# modulator-switch.net
KiCad netlist of a schematic drawn in EAGLE
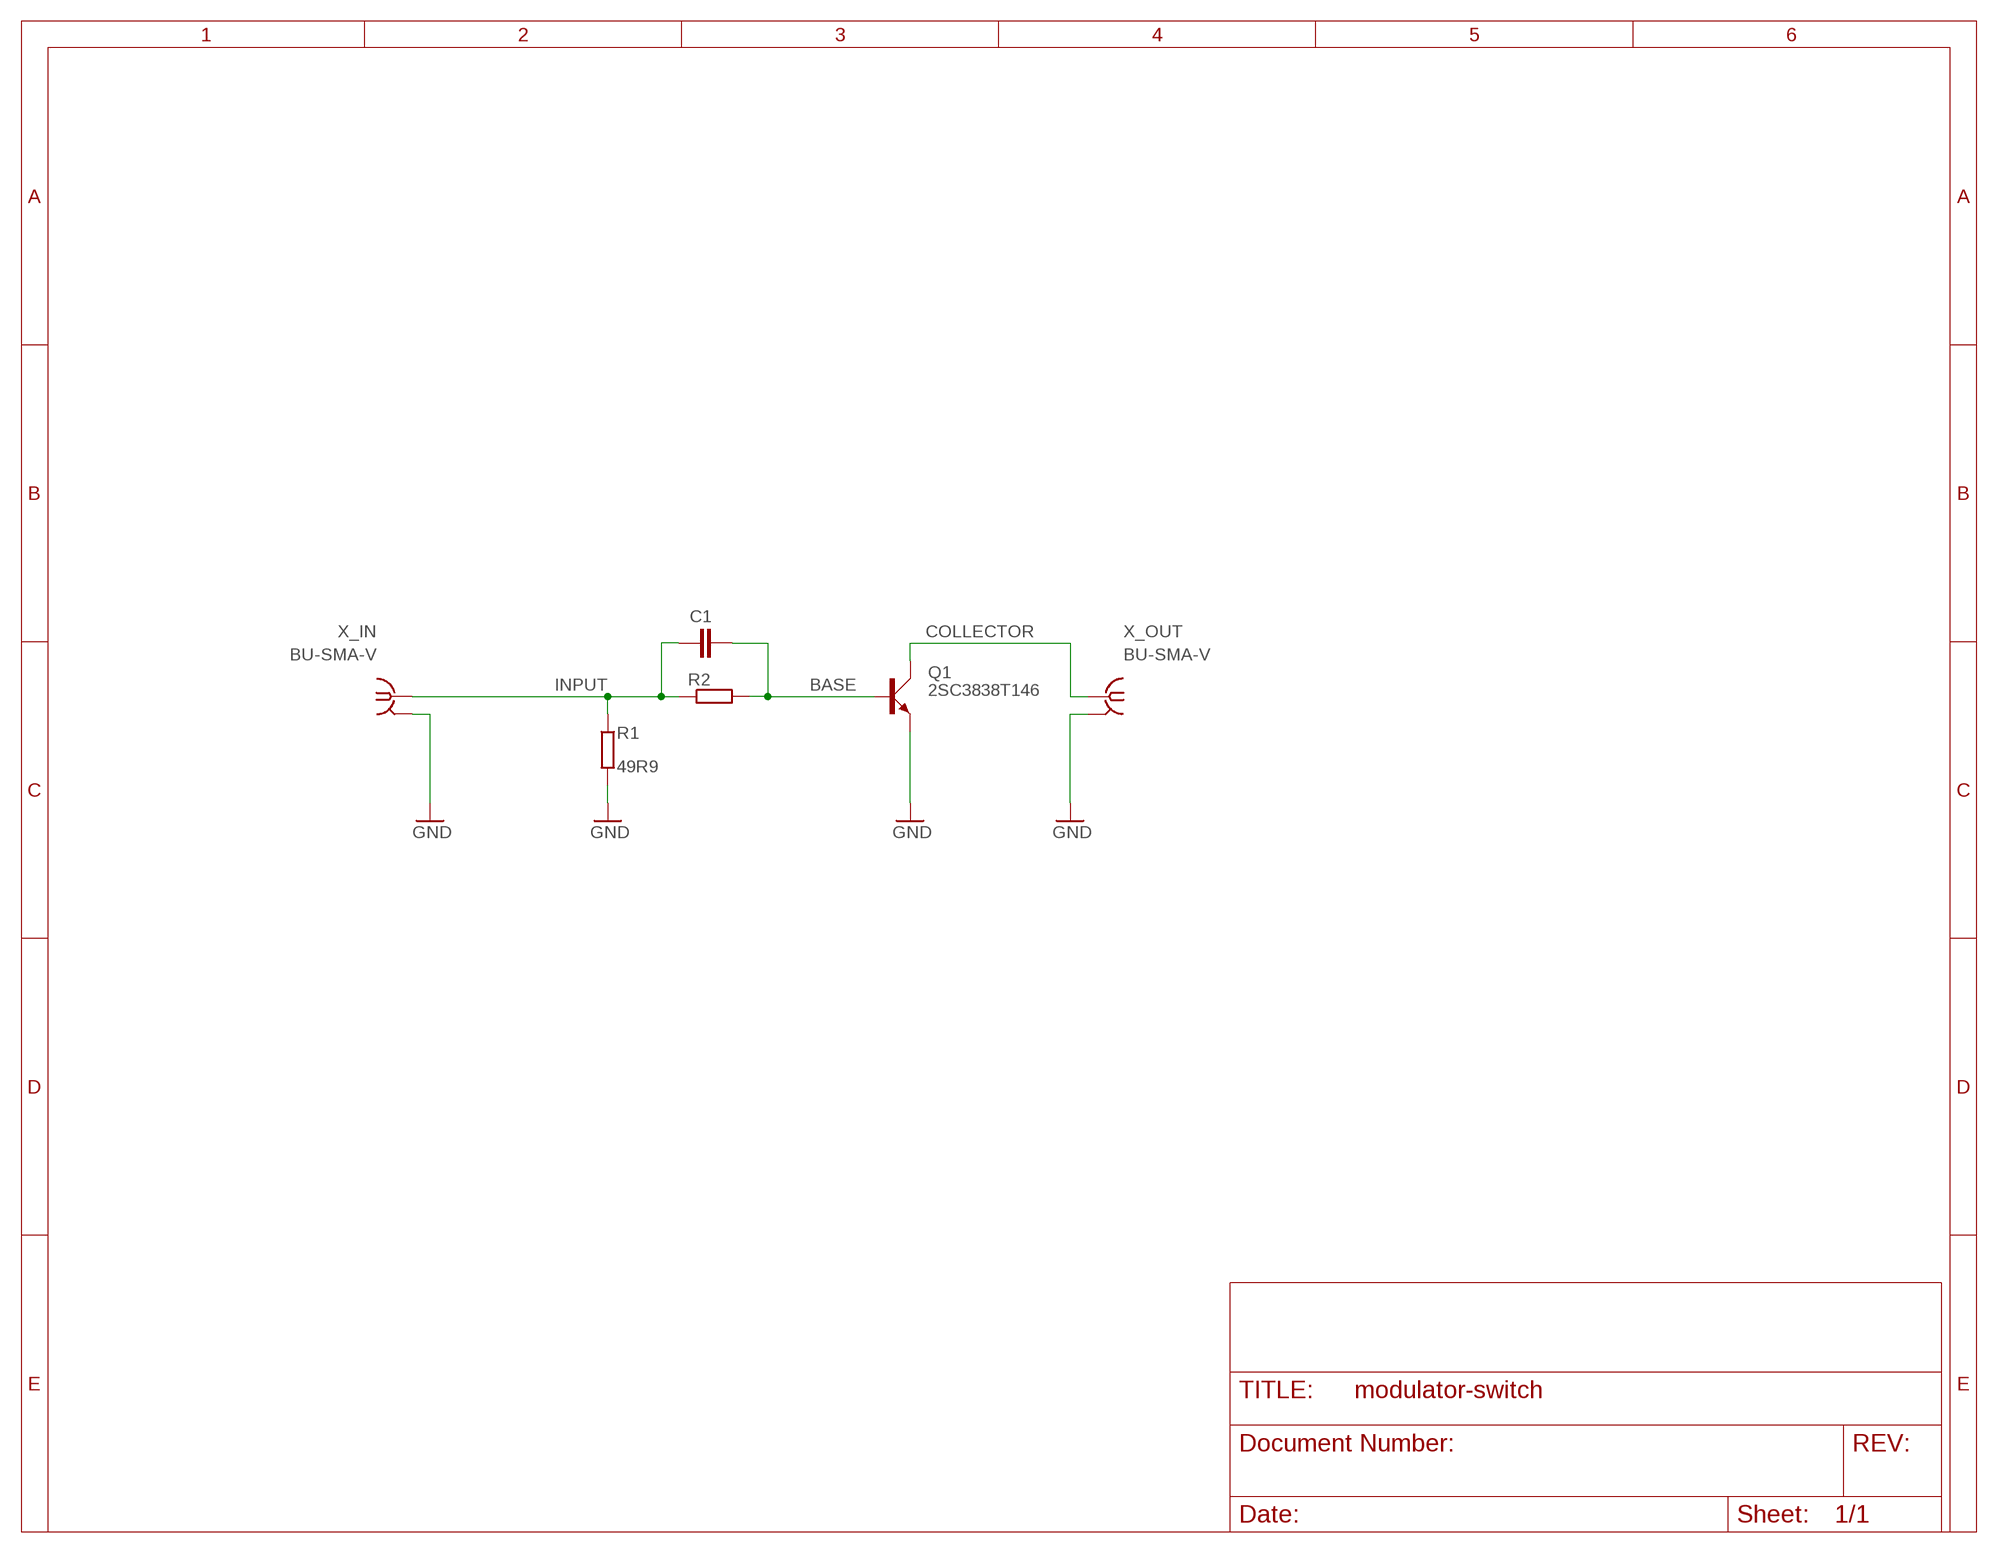
[diagram p0: schematic, sheet 1]

(export (version "E")
  (design (tool "Eeschema 10.0.6"))
  (components
    (comp (ref "C1")
      (value "C-EUC0603")
      (footprint "eagle-import:C0603")
      (libsource (lib "eagle-import") (part "C-EUC0603"))
    )
    (comp (ref "Q1")
      (value "2SC3838T146")
      (footprint "eagle-import:SC59")
      (libsource (lib "eagle-import") (part "2SC3838T146"))
    )
    (comp (ref "R1")
      (value "49R9")
      (footprint "eagle-import:R0805")
      (libsource (lib "eagle-import") (part "R-EU_R0805"))
    )
    (comp (ref "R2")
      (value "R-EU_R0603")
      (footprint "eagle-import:R0603")
      (libsource (lib "eagle-import") (part "R-EU_R0603"))
    )
    (comp (ref "X_IN")
      (value "BU-SMA-V")
      (footprint "eagle-import:BU-SMA-V")
      (libsource (lib "eagle-import") (part "BU-SMA-V"))
    )
    (comp (ref "X_OUT")
      (value "BU-SMA-V")
      (footprint "eagle-import:BU-SMA-V")
      (libsource (lib "eagle-import") (part "BU-SMA-V"))
    )
  )
  (nets
    (net (code "1") (name "/BASE") (class "Default")
      (node (ref "C1") (pin "2") (pinfunction "2_2") (pintype "passive"))
      (node (ref "Q1") (pin "B") (pinfunction "B_B") (pintype "passive"))
      (node (ref "R2") (pin "2") (pinfunction "2_2") (pintype "passive"))
    )
    (net (code "2") (name "/COLLECTOR") (class "Default")
      (node (ref "Q1") (pin "C") (pinfunction "C_C") (pintype "passive"))
      (node (ref "X_OUT") (pin "1") (pinfunction "1_1") (pintype "passive"))
    )
    (net (code "3") (name "/INPUT") (class "Default")
      (node (ref "C1") (pin "1") (pinfunction "1_1") (pintype "passive"))
      (node (ref "R1") (pin "1") (pinfunction "1_1") (pintype "passive"))
      (node (ref "R2") (pin "1") (pinfunction "1_1") (pintype "passive"))
      (node (ref "X_IN") (pin "1") (pinfunction "1_1") (pintype "passive"))
    )
    (net (code "4") (name "GND") (class "Default")
      (node (ref "Q1") (pin "E") (pinfunction "E_E") (pintype "passive"))
      (node (ref "R1") (pin "2") (pinfunction "2_2") (pintype "passive"))
      (node (ref "X_IN") (pin "2") (pinfunction "GND_2") (pintype "power_in"))
      (node (ref "X_OUT") (pin "2") (pinfunction "GND_2") (pintype "power_in"))
    )
  )
)
